# Power.net
KiCad netlist of a schematic drawn in Altium Designer
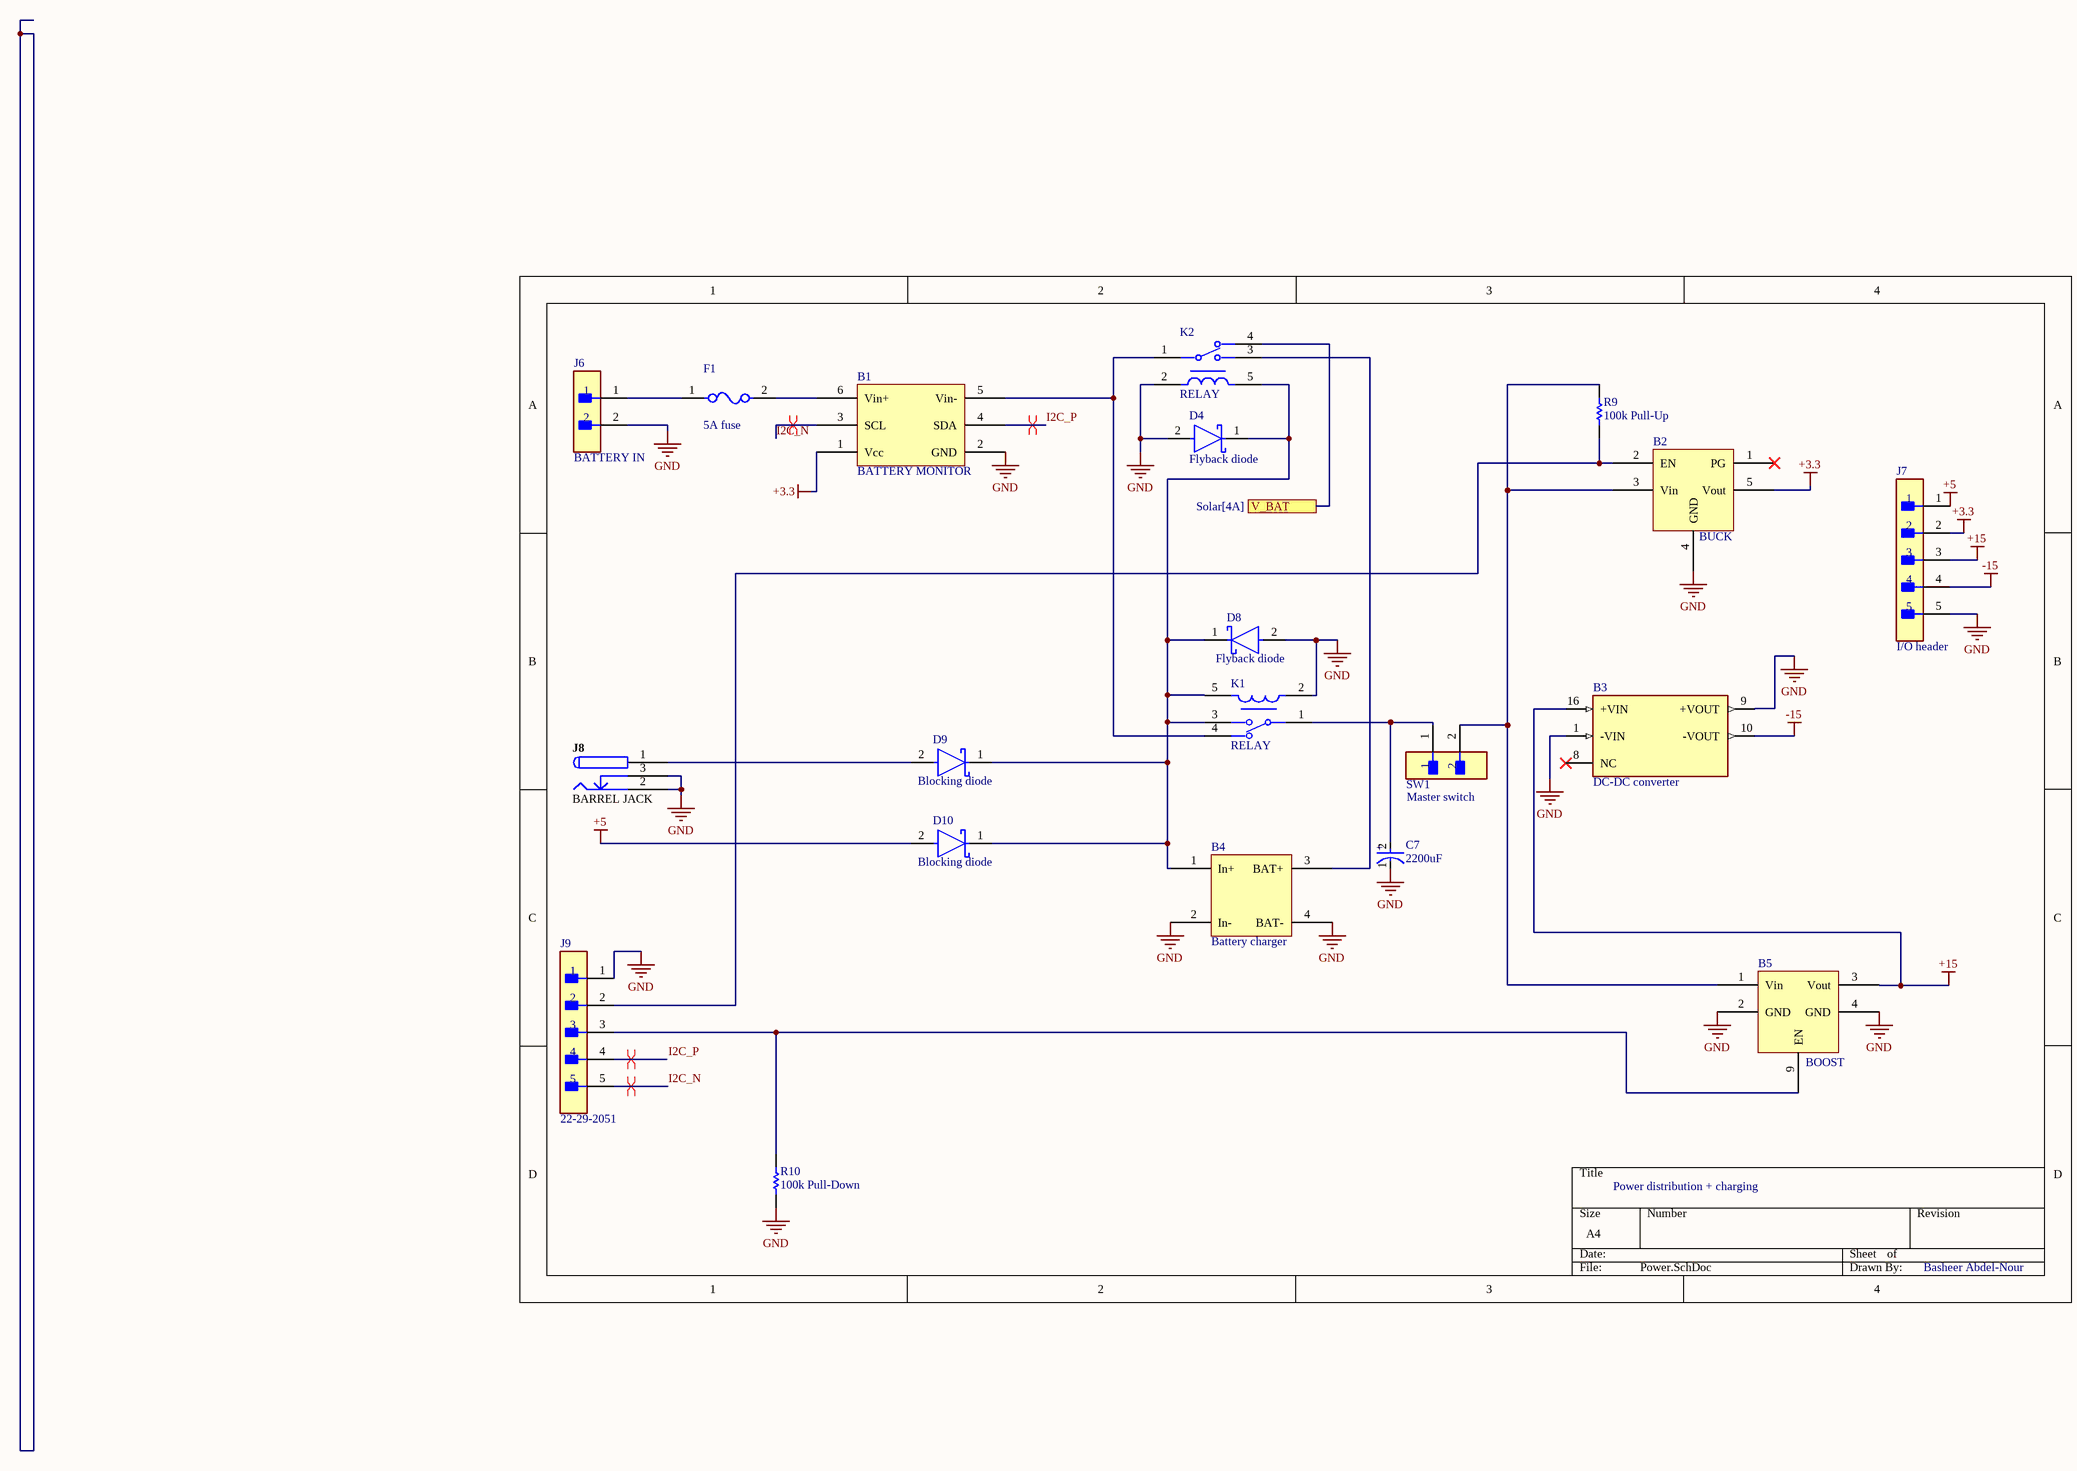
[diagram p0: Power.SchDoc]

(export (version "E")
  (design (tool "Eeschema 10.0.6"))
  (components
    (comp (ref "B1")
      (value "BATTERY MONITOR")
      (footprint "Adafruit 904")
      (libsource (lib "Breakout boards") (part "Adafruit 904"))
    )
    (comp (ref "B2")
      (value "BUCK")
      (footprint "Pololu Buck converter")
      (libsource (lib "Breakout boards") (part "Pololu_buck"))
    )
    (comp (ref "B3")
      (value "DC-DC converter")
      (footprint "DC-DC converter")
      (libsource (lib "Breakout boards") (part "DC-DC converter"))
    )
    (comp (ref "B4")
      (value "Battery charger")
      (footprint "Battery charger")
      (libsource (lib "Breakout boards") (part "Battery charger"))
    )
    (comp (ref "B5")
      (value "BOOST")
      (footprint "Pololu boost converter")
      (libsource (lib "Breakout boards") (part "Pololu_boost"))
    )
    (comp (ref "C7")
      (value "2200uF")
      (footprint "FP-RAD-TH-D_16_0_5-L_25_2-MFG")
      (description "Aluminum Electrolytic Capacitors (Radial Lead Type) AEC-Q200 Qualified 2200uF ±20% 25V")
      (fields (field (name "TOLERANCE") "20%") (field (name "VOLTAGE") "25V"))
      (libsource (lib "Altium Content Vault") (part "203bc49f2ac43e59fd269a8c329ed05"))
    )
    (comp (ref "D4")
      (value "Flyback diode")
      (footprint "FP-DO-201AD-MFG")
      (description "DIODE SCHOTTKY 40V 3A DO201AD")
      (fields
        (field (name "MANUFACTURER PART NUMBER") "1N5822")
        (field (name "OCTOPART") "https://octopart.com/1n5822-stmicroelectronics-323225")
      )
      (libsource (lib "Altium Content Vault") (part "1d6ec82d83fb6aee721767c19dac4b9"))
    )
    (comp (ref "D8")
      (value "Flyback diode")
      (footprint "FP-DO-201AD-MFG")
      (description "DIODE SCHOTTKY 40V 3A DO201AD")
      (fields
        (field (name "MANUFACTURER PART NUMBER") "1N5822")
        (field (name "OCTOPART") "https://octopart.com/1n5822-stmicroelectronics-323225")
      )
      (libsource (lib "Altium Content Vault") (part "1d6ec82d83fb6aee721767c19dac4b9"))
    )
    (comp (ref "D9")
      (value "Blocking diode")
      (footprint "FP-DO-201AD-MFG")
      (description "DIODE SCHOTTKY 40V 3A DO201AD")
      (fields
        (field (name "MANUFACTURER PART NUMBER") "1N5822")
        (field (name "OCTOPART") "https://octopart.com/1n5822-stmicroelectronics-323225")
      )
      (libsource (lib "Altium Content Vault") (part "1d6ec82d83fb6aee721767c19dac4b9"))
    )
    (comp (ref "D10")
      (value "Blocking diode")
      (footprint "FP-DO-201AD-MFG")
      (description "DIODE SCHOTTKY 40V 3A DO201AD")
      (fields
        (field (name "MANUFACTURER PART NUMBER") "1N5822")
        (field (name "OCTOPART") "https://octopart.com/1n5822-stmicroelectronics-323225")
      )
      (libsource (lib "Altium Content Vault") (part "1d6ec82d83fb6aee721767c19dac4b9"))
    )
    (comp (ref "F1")
      (value "5A fuse")
      (footprint "FP-0PTF0078P-MFG")
      (description "FUSE BLOCK CARTRIDGE PCB")
      (fields
        (field (name "MANUFACTURER PART NUMBER") "0PTF0078P")
        (field (name "OCTOPART") "https://octopart.com/0ptf0078p-littelfuse-13255855")
      )
      (libsource (lib "Altium Content Vault") (part "5bcf9b9f640e542cf0359d10258e979"))
    )
    (comp (ref "J6")
      (value "BATTERY IN")
      (footprint "FP-26-61-4020-MFG")
      (libsource (lib "Altium Content Vault") (part "3bc925449376181038e59eaffc5286c"))
    )
    (comp (ref "J7")
      (value "I/O header")
      (footprint "FP-26-60-4050-MFG")
      (description "CONN HEADER VERT 5POS 3.96MM")
      (libsource (lib "Altium Content Vault") (part "bf93c07fd2649a848d0ec8585582aab"))
    )
    (comp (ref "J8")
      (value "BARREL JACK")
      (footprint "KYCN-KLDX-0202-B_V")
      (description "3 Conductor Power Jack, 2 break 2 aux contacts")
      (fields (field (name "PARTNUMBER") "KLDX-0202-B"))
      (libsource (lib "Altium Content Vault") (part "KYCN-KLDX-0202-B-3"))
    )
    (comp (ref "J9")
      (value "22-29-2051")
      (footprint "FP-22-29-2051-MFG")
      (description "2.54MM KK HDR VT FRICLK VRA .5AU")
      (libsource (lib "Altium Content Vault") (part "bf93c07fd2649a848d0ec8585582aab"))
    )
    (comp (ref "K1")
      (value "RELAY")
      (footprint "FP-G5LE-1-E_DC5-MFG")
      (description "RELAY GEN PURPOSE SPDT 16A 5V")
      (libsource (lib "Altium Content Vault") (part "c03b8d08e5d02e70a6880f365e34168"))
    )
    (comp (ref "K2")
      (value "RELAY")
      (footprint "FP-G5LE-1-E_DC5-MFG")
      (description "RELAY GEN PURPOSE SPDT 16A 5V")
      (libsource (lib "Altium Content Vault") (part "c03b8d08e5d02e70a6880f365e34168"))
    )
    (comp (ref "R9")
      (value "100k Pull-Up")
      (footprint "RESA60-630X240")
      (description "Axial Resistor, 100 KOhm, +/- 1%, 0.25 W, -55 to 155 degC, 2-Pin THD, RoHS, Bulk")
      (fields (field (name "TOLERANCE") "1%"))
      (libsource (lib "Altium Content Vault") (part "RES-2"))
    )
    (comp (ref "R10")
      (value "100k Pull-Down")
      (footprint "RESA60-630X240")
      (description "Axial Resistor, 100 KOhm, +/- 1%, 0.25 W, -55 to 155 degC, 2-Pin THD, RoHS, Bulk")
      (fields (field (name "TOLERANCE") "1%"))
      (libsource (lib "Altium Content Vault") (part "RES-2"))
    )
    (comp (ref "SW1")
      (value "Master switch")
      (footprint "FP-26-61-4020-MFG")
      (libsource (lib "") (part "3bc925449376181038e59eaffc5286c_1"))
    )
  )
  (nets
    (net (code "1") (name "+3.3") (class "Default")
      (node (ref "B1") (pin "1") (pinfunction "Vcc_1") (pintype "passive"))
      (node (ref "B2") (pin "5") (pinfunction "Vout_5") (pintype "passive"))
      (node (ref "J7") (pin "2") (pinfunction "2_2") (pintype "passive"))
    )
    (net (code "2") (name "+5") (class "Default")
      (node (ref "D10") (pin "2") (pinfunction "A_2") (pintype "passive"))
      (node (ref "J7") (pin "1") (pinfunction "1_1") (pintype "passive"))
    )
    (net (code "3") (name "+15") (class "Default")
      (node (ref "B3") (pin "16") (pinfunction "+VIN_16") (pintype "input"))
      (node (ref "B5") (pin "3") (pinfunction "Vout_3") (pintype "passive"))
      (node (ref "J7") (pin "3") (pinfunction "3_3") (pintype "passive"))
    )
    (net (code "4") (name "-15") (class "Default")
      (node (ref "B3") (pin "10") (pinfunction "-VOUT_10") (pintype "output"))
      (node (ref "J7") (pin "4") (pinfunction "4_4") (pintype "passive"))
    )
    (net (code "5") (name "/I2C_N") (class "Default")
      (node (ref "B1") (pin "3") (pinfunction "SCL_3") (pintype "passive"))
      (node (ref "J9") (pin "5") (pinfunction "5_5") (pintype "passive"))
    )
    (net (code "6") (name "/I2C_P") (class "Default")
      (node (ref "B1") (pin "4") (pinfunction "SDA_4") (pintype "passive"))
    )
    (net (code "7") (name "/V_BAT") (class "Default")
      (node (ref "K2") (pin "4") (pinfunction "4_4") (pintype "passive"))
    )
    (net (code "8") (name "GND") (class "Default")
      (node (ref "B1") (pin "2") (pinfunction "GND_2") (pintype "passive"))
      (node (ref "B2") (pin "4") (pinfunction "GND_4") (pintype "passive"))
      (node (ref "B3") (pin "1") (pinfunction "-VIN_1") (pintype "input"))
      (node (ref "B3") (pin "9") (pinfunction "+VOUT_9") (pintype "output"))
      (node (ref "B4") (pin "2") (pinfunction "In-_2") (pintype "passive"))
      (node (ref "B4") (pin "4") (pinfunction "BAT-_4") (pintype "passive"))
      (node (ref "B5") (pin "2") (pinfunction "GND_2") (pintype "passive"))
      (node (ref "B5") (pin "4") (pinfunction "GND_4") (pintype "passive"))
      (node (ref "C7") (pin "1") (pinfunction "C_1") (pintype "passive"))
      (node (ref "D4") (pin "2") (pinfunction "A_2") (pintype "passive"))
      (node (ref "D8") (pin "2") (pinfunction "A_2") (pintype "passive"))
      (node (ref "J6") (pin "2") (pinfunction "2_2") (pintype "passive"))
      (node (ref "J7") (pin "5") (pinfunction "5_5") (pintype "passive"))
      (node (ref "J8") (pin "2") (pintype "power_in"))
      (node (ref "J8") (pin "3") (pintype "power_in"))
      (node (ref "J9") (pin "1") (pinfunction "1_1") (pintype "passive"))
      (node (ref "K1") (pin "2") (pinfunction "2_2") (pintype "passive"))
      (node (ref "K2") (pin "2") (pinfunction "2_2") (pintype "passive"))
      (node (ref "R10") (pin "1") (pinfunction "1_1") (pintype "passive"))
    )
    (net (code "9") (name "Net-(B1-Vin+)") (class "Default")
      (node (ref "B1") (pin "6") (pinfunction "Vin+_6") (pintype "passive"))
      (node (ref "F1") (pin "2") (pinfunction "2_2") (pintype "passive"))
    )
    (net (code "10") (name "Net-(B1-Vin-)") (class "Default")
      (node (ref "B1") (pin "5") (pinfunction "Vin-_5") (pintype "passive"))
      (node (ref "K1") (pin "4") (pinfunction "4_4") (pintype "passive"))
      (node (ref "K2") (pin "1") (pinfunction "1_1") (pintype "passive"))
    )
    (net (code "11") (name "Net-(B2-EN)") (class "Default")
      (node (ref "B2") (pin "2") (pinfunction "EN_2") (pintype "passive"))
      (node (ref "J9") (pin "2") (pinfunction "2_2") (pintype "passive"))
      (node (ref "R9") (pin "1") (pinfunction "1_1") (pintype "passive"))
    )
    (net (code "12") (name "Net-(B2-Vin)") (class "Default")
      (node (ref "B2") (pin "3") (pinfunction "Vin_3") (pintype "passive"))
      (node (ref "B5") (pin "1") (pinfunction "Vin_1") (pintype "passive"))
      (node (ref "R9") (pin "2") (pinfunction "2_2") (pintype "passive"))
      (node (ref "SW1") (pin "2") (pinfunction "2_2") (pintype "passive"))
    )
    (net (code "13") (name "Net-(B4-BAT+)") (class "Default")
      (node (ref "B4") (pin "3") (pinfunction "BAT+_3") (pintype "passive"))
      (node (ref "K2") (pin "3") (pinfunction "3_3") (pintype "passive"))
    )
    (net (code "14") (name "Net-(B4-In+)") (class "Default")
      (node (ref "B4") (pin "1") (pinfunction "In+_1") (pintype "passive"))
      (node (ref "D10") (pin "1") (pinfunction "C_1") (pintype "passive"))
      (node (ref "D4") (pin "1") (pinfunction "C_1") (pintype "passive"))
      (node (ref "D8") (pin "1") (pinfunction "C_1") (pintype "passive"))
      (node (ref "D9") (pin "1") (pinfunction "C_1") (pintype "passive"))
      (node (ref "K1") (pin "3") (pinfunction "3_3") (pintype "passive"))
      (node (ref "K1") (pin "5") (pinfunction "5_5") (pintype "passive"))
      (node (ref "K2") (pin "5") (pinfunction "5_5") (pintype "passive"))
    )
    (net (code "15") (name "Net-(B5-EN)") (class "Default")
      (node (ref "B5") (pin "9") (pinfunction "EN_9") (pintype "passive"))
      (node (ref "J9") (pin "3") (pinfunction "3_3") (pintype "passive"))
      (node (ref "R10") (pin "2") (pinfunction "2_2") (pintype "passive"))
    )
    (net (code "16") (name "Net-(C7-A)") (class "Default")
      (node (ref "C7") (pin "2") (pinfunction "A_2") (pintype "passive"))
      (node (ref "K1") (pin "1") (pinfunction "1_1") (pintype "passive"))
      (node (ref "SW1") (pin "1") (pinfunction "1_1") (pintype "passive"))
    )
    (net (code "17") (name "Net-(D9-A)") (class "Default")
      (node (ref "D9") (pin "2") (pinfunction "A_2") (pintype "passive"))
      (node (ref "J8") (pin "1") (pintype "power_in"))
    )
    (net (code "18") (name "Net-(F1-Pad1)") (class "Default")
      (node (ref "F1") (pin "1") (pinfunction "1_1") (pintype "passive"))
      (node (ref "J6") (pin "1") (pinfunction "1_1") (pintype "passive"))
    )
    (net (code "19") (name "unconnected-(B2-PG-Pad1)") (class "Default")
      (node (ref "B2") (pin "1") (pinfunction "PG_1") (pintype "passive+no_connect"))
    )
    (net (code "20") (name "unconnected-(B3-NC-Pad8)") (class "Default")
      (node (ref "B3") (pin "8") (pinfunction "NC_8") (pintype "passive+no_connect"))
    )
    (net (code "21") (name "unconnected-(J9-Pad4)") (class "Default")
      (node (ref "J9") (pin "4") (pinfunction "4_4") (pintype "passive"))
    )
  )
)
